# Pro_Micro.net
KiCad netlist of a schematic drawn in EAGLE
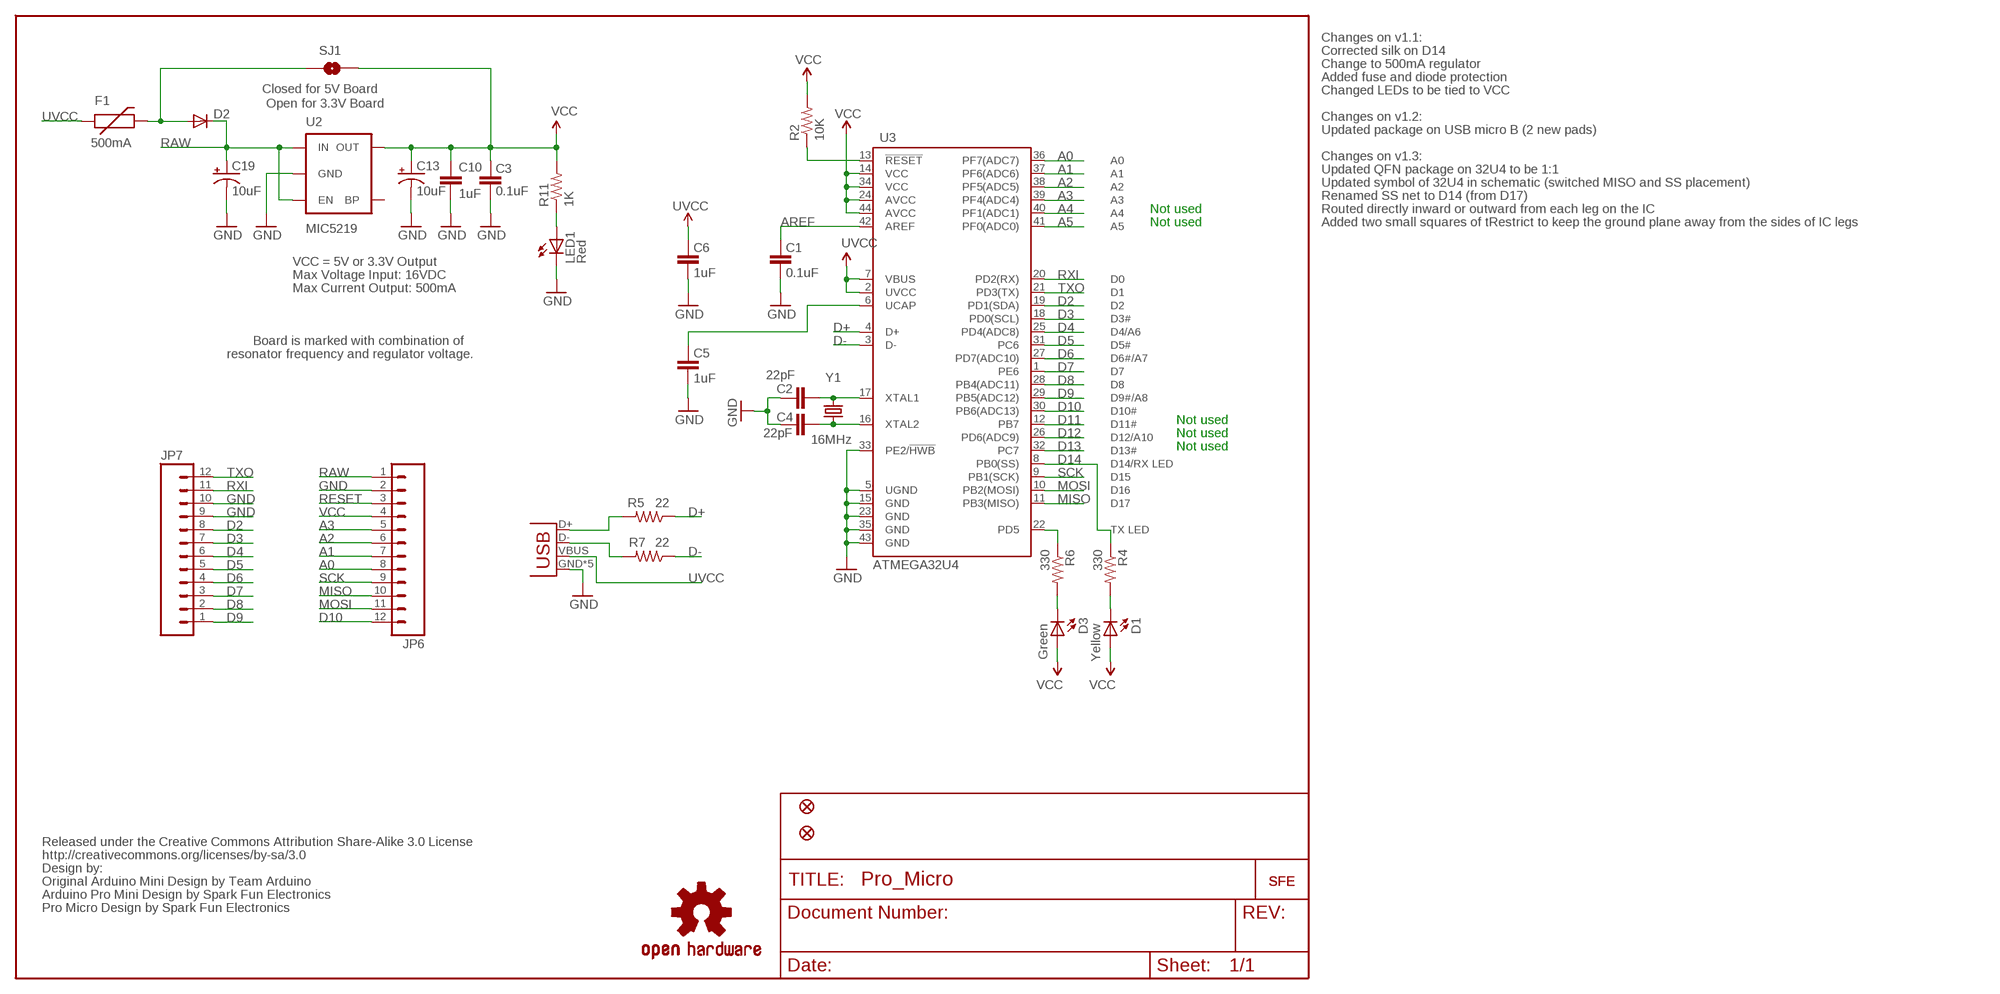
[diagram p0: schematic, sheet 1]

(export (version "E")
  (design (tool "Eeschema 10.0.6"))
  (components
    (comp (ref "C1")
      (value "0.1uF")
      (footprint "eagle-import:0603-CAP")
      (libsource (lib "eagle-import") (part "CAP0603-CAP"))
    )
    (comp (ref "C2")
      (value "22pF")
      (footprint "eagle-import:0603-CAP")
      (libsource (lib "eagle-import") (part "CAP0603-CAP"))
    )
    (comp (ref "C3")
      (value "0.1uF")
      (footprint "eagle-import:0603-CAP")
      (libsource (lib "eagle-import") (part "CAP0603-CAP"))
    )
    (comp (ref "C4")
      (value "22pF")
      (footprint "eagle-import:0603-CAP")
      (libsource (lib "eagle-import") (part "CAP0603-CAP"))
    )
    (comp (ref "C5")
      (value "1uF")
      (footprint "eagle-import:0603-CAP")
      (libsource (lib "eagle-import") (part "CAP0603-CAP"))
    )
    (comp (ref "C6")
      (value "1uF")
      (footprint "eagle-import:0603-CAP")
      (libsource (lib "eagle-import") (part "CAP0603-CAP"))
    )
    (comp (ref "C10")
      (value "1uF")
      (footprint "eagle-import:0603-CAP")
      (libsource (lib "eagle-import") (part "CAP0603-CAP"))
    )
    (comp (ref "C13")
      (value "10uF")
      (footprint "eagle-import:EIA3216")
      (libsource (lib "eagle-import") (part "CAP_POL1206"))
    )
    (comp (ref "C19")
      (value "10uF")
      (footprint "eagle-import:EIA3216")
      (libsource (lib "eagle-import") (part "CAP_POL1206"))
    )
    (comp (ref "D1")
      (value "Yellow")
      (footprint "eagle-import:LED-0603")
      (libsource (lib "eagle-import") (part "LED0603"))
    )
    (comp (ref "D2")
      (value "DIODESOD")
      (footprint "eagle-import:SOD-323")
      (libsource (lib "eagle-import") (part "DIODESOD"))
    )
    (comp (ref "D3")
      (value "Green")
      (footprint "eagle-import:LED-0603")
      (libsource (lib "eagle-import") (part "LED0603"))
    )
    (comp (ref "F1")
      (value "500mA")
      (footprint "eagle-import:PTC-1206")
      (libsource (lib "eagle-import") (part "PTCSMD"))
    )
    (comp (ref "JP1")
      (value "FIDUCIALUFIDUCIAL")
      (footprint "eagle-import:MICRO-FIDUCIAL")
      (libsource (lib "eagle-import") (part "FIDUCIALUFIDUCIAL"))
    )
    (comp (ref "JP2")
      (value "FIDUCIALUFIDUCIAL")
      (footprint "eagle-import:MICRO-FIDUCIAL")
      (libsource (lib "eagle-import") (part "FIDUCIALUFIDUCIAL"))
    )
    (comp (ref "JP6")
      (value "M12PTH")
      (footprint "eagle-import:1X12")
      (libsource (lib "eagle-import") (part "M12PTH"))
    )
    (comp (ref "JP7")
      (value "M12PTH")
      (footprint "eagle-import:1X12")
      (libsource (lib "eagle-import") (part "M12PTH"))
    )
    (comp (ref "LED1")
      (value "Red")
      (footprint "eagle-import:LED-0603")
      (libsource (lib "eagle-import") (part "LED0603"))
    )
    (comp (ref "R2")
      (value "10K")
      (footprint "eagle-import:0603-RES")
      (libsource (lib "eagle-import") (part "RESISTOR0603-RES"))
    )
    (comp (ref "R4")
      (value "330")
      (footprint "eagle-import:0603-RES")
      (libsource (lib "eagle-import") (part "RESISTOR0603-RES"))
    )
    (comp (ref "R5")
      (value "22")
      (footprint "eagle-import:0603-RES")
      (libsource (lib "eagle-import") (part "RESISTOR0603-RES"))
    )
    (comp (ref "R6")
      (value "330")
      (footprint "eagle-import:0603-RES")
      (libsource (lib "eagle-import") (part "RESISTOR0603-RES"))
    )
    (comp (ref "R7")
      (value "22")
      (footprint "eagle-import:0603-RES")
      (libsource (lib "eagle-import") (part "RESISTOR0603-RES"))
    )
    (comp (ref "R11")
      (value "1K")
      (footprint "eagle-import:0603-RES")
      (libsource (lib "eagle-import") (part "RESISTOR0603-RES"))
    )
    (comp (ref "SJ1")
      (value "Closed for 5V Board")
      (footprint "eagle-import:SJ_2S")
      (libsource (lib "eagle-import") (part "SOLDERJUMPERNC"))
    )
    (comp (ref "U$1")
      (value "LOGO-SFESK")
      (footprint "eagle-import:SFE-LOGO-FLAME")
      (libsource (lib "eagle-import") (part "LOGO-SFESK"))
    )
    (comp (ref "U$3")
      (value "OSHW-LOGOS")
      (footprint "eagle-import:OSHW-LOGO-S")
      (libsource (lib "eagle-import") (part "OSHW-LOGOS"))
    )
    (comp (ref "U$5")
      (value "CREATIVE_COMMONS")
      (footprint "eagle-import:CREATIVE_COMMONS")
      (libsource (lib "eagle-import") (part "CREATIVE_COMMONS"))
    )
    (comp (ref "U$11")
      (value "LOGO-SFENEW")
      (footprint "eagle-import:SFE-NEW-WEBLOGO")
      (libsource (lib "eagle-import") (part "LOGO-SFENEW"))
    )
    (comp (ref "U2")
      (value "MIC5219")
      (footprint "eagle-import:SOT23-5")
      (libsource (lib "eagle-import") (part "V_REG_LDOSMD"))
    )
    (comp (ref "U3")
      (value "ATMEGA32U4")
      (footprint "eagle-import:QFN-44-NOPAD_1_1")
      (libsource (lib "eagle-import") (part "ATMEGA32U41{colon}1"))
    )
    (comp (ref "X1")
      (value "USB-MICROB")
      (footprint "eagle-import:USB-MICROB")
      (libsource (lib "eagle-import") (part "USB-MICROB"))
    )
    (comp (ref "Y1")
      (value "16MHz")
      (footprint "eagle-import:CRYSTAL-SMD-5X3")
      (libsource (lib "eagle-import") (part "CRYSTAL5X3"))
    )
  )
  (nets
    (net (code "1") (name "/A0") (class "Default")
      (node (ref "JP6") (pin "8") (pinfunction "8_8") (pintype "passive"))
      (node (ref "U3") (pin "36") (pinfunction "PF7(ADC7)_36") (pintype "bidirectional"))
    )
    (net (code "2") (name "/A1") (class "Default")
      (node (ref "JP6") (pin "7") (pinfunction "7_7") (pintype "passive"))
      (node (ref "U3") (pin "37") (pinfunction "PF6(ADC6)_37") (pintype "bidirectional"))
    )
    (net (code "3") (name "/A2") (class "Default")
      (node (ref "JP6") (pin "6") (pinfunction "6_6") (pintype "passive"))
      (node (ref "U3") (pin "38") (pinfunction "PF5(ADC5)_38") (pintype "bidirectional"))
    )
    (net (code "4") (name "/A3") (class "Default")
      (node (ref "JP6") (pin "5") (pinfunction "5_5") (pintype "passive"))
      (node (ref "U3") (pin "39") (pinfunction "PF4(ADC4)_39") (pintype "bidirectional"))
    )
    (net (code "5") (name "/A4") (class "Default")
      (node (ref "U3") (pin "40") (pinfunction "PF1(ADC1)_40") (pintype "bidirectional"))
    )
    (net (code "6") (name "/A5") (class "Default")
      (node (ref "U3") (pin "41") (pinfunction "PF0(ADC0)_41") (pintype "bidirectional"))
    )
    (net (code "7") (name "/AREF") (class "Default")
      (node (ref "C1") (pin "2") (pinfunction "2_2") (pintype "passive"))
      (node (ref "U3") (pin "42") (pinfunction "AREF_42") (pintype "bidirectional"))
    )
    (net (code "8") (name "/D+") (class "Default")
      (node (ref "R5") (pin "1") (pinfunction "1_1") (pintype "passive"))
      (node (ref "U3") (pin "4") (pinfunction "D+_4") (pintype "bidirectional"))
    )
    (net (code "9") (name "/D-") (class "Default")
      (node (ref "R7") (pin "1") (pinfunction "1_1") (pintype "passive"))
      (node (ref "U3") (pin "3") (pinfunction "D-_3") (pintype "bidirectional"))
    )
    (net (code "10") (name "/D2") (class "Default")
      (node (ref "JP7") (pin "8") (pinfunction "8_8") (pintype "passive"))
      (node (ref "U3") (pin "19") (pinfunction "PD1(SDA)_19") (pintype "bidirectional"))
    )
    (net (code "11") (name "/D3") (class "Default")
      (node (ref "JP7") (pin "7") (pinfunction "7_7") (pintype "passive"))
      (node (ref "U3") (pin "18") (pinfunction "PD0(SCL)_18") (pintype "bidirectional"))
    )
    (net (code "12") (name "/D4") (class "Default")
      (node (ref "JP7") (pin "6") (pinfunction "6_6") (pintype "passive"))
      (node (ref "U3") (pin "25") (pinfunction "PD4(ADC8)_25") (pintype "bidirectional"))
    )
    (net (code "13") (name "/D5") (class "Default")
      (node (ref "JP7") (pin "5") (pinfunction "5_5") (pintype "passive"))
      (node (ref "U3") (pin "31") (pinfunction "PC6_31") (pintype "bidirectional"))
    )
    (net (code "14") (name "/D6") (class "Default")
      (node (ref "JP7") (pin "4") (pinfunction "4_4") (pintype "passive"))
      (node (ref "U3") (pin "27") (pinfunction "PD7(ADC10)_27") (pintype "bidirectional"))
    )
    (net (code "15") (name "/D7") (class "Default")
      (node (ref "JP7") (pin "3") (pinfunction "3_3") (pintype "passive"))
      (node (ref "U3") (pin "1") (pinfunction "PE6_1") (pintype "bidirectional"))
    )
    (net (code "16") (name "/D8") (class "Default")
      (node (ref "JP7") (pin "2") (pinfunction "2_2") (pintype "passive"))
      (node (ref "U3") (pin "28") (pinfunction "PB4(ADC11)_28") (pintype "bidirectional"))
    )
    (net (code "17") (name "/D9") (class "Default")
      (node (ref "JP7") (pin "1") (pinfunction "1_1") (pintype "passive"))
      (node (ref "U3") (pin "29") (pinfunction "PB5(ADC12)_29") (pintype "bidirectional"))
    )
    (net (code "18") (name "/D10") (class "Default")
      (node (ref "JP6") (pin "12") (pinfunction "12_12") (pintype "passive"))
      (node (ref "U3") (pin "30") (pinfunction "PB6(ADC13)_30") (pintype "bidirectional"))
    )
    (net (code "19") (name "/D11") (class "Default")
      (node (ref "U3") (pin "12") (pinfunction "PB7_12") (pintype "bidirectional"))
    )
    (net (code "20") (name "/D12") (class "Default")
      (node (ref "U3") (pin "26") (pinfunction "PD6(ADC9)_26") (pintype "bidirectional"))
    )
    (net (code "21") (name "/D13") (class "Default")
      (node (ref "U3") (pin "32") (pinfunction "PC7_32") (pintype "bidirectional"))
    )
    (net (code "22") (name "/D14") (class "Default")
      (node (ref "R4") (pin "1") (pinfunction "1_1") (pintype "passive"))
      (node (ref "U3") (pin "8") (pinfunction "PB0(SS)_8") (pintype "bidirectional"))
    )
    (net (code "23") (name "/MISO") (class "Default")
      (node (ref "JP6") (pin "10") (pinfunction "10_10") (pintype "passive"))
      (node (ref "U3") (pin "11") (pinfunction "PB3(MISO)_11") (pintype "bidirectional"))
    )
    (net (code "24") (name "/MOSI") (class "Default")
      (node (ref "JP6") (pin "11") (pinfunction "11_11") (pintype "passive"))
      (node (ref "U3") (pin "10") (pinfunction "PB2(MOSI)_10") (pintype "bidirectional"))
    )
    (net (code "25") (name "/RAW") (class "Default")
      (node (ref "C19") (pin "A") (pinfunction "+_A") (pintype "passive"))
      (node (ref "D2") (pin "1") (pinfunction "C_1") (pintype "passive"))
      (node (ref "JP6") (pin "1") (pinfunction "1_1") (pintype "passive"))
      (node (ref "U2") (pin "1") (pinfunction "IN_1") (pintype "input"))
      (node (ref "U2") (pin "3") (pinfunction "EN_3") (pintype "input"))
    )
    (net (code "26") (name "/RESET") (class "Default")
      (node (ref "JP6") (pin "3") (pinfunction "3_3") (pintype "passive"))
      (node (ref "R2") (pin "1") (pinfunction "1_1") (pintype "passive"))
      (node (ref "U3") (pin "13") (pinfunction "~{RESET}_13") (pintype "bidirectional"))
    )
    (net (code "27") (name "/RXI") (class "Default")
      (node (ref "JP7") (pin "11") (pinfunction "11_11") (pintype "passive"))
      (node (ref "U3") (pin "20") (pinfunction "PD2(RX)_20") (pintype "bidirectional"))
    )
    (net (code "28") (name "/SCK") (class "Default")
      (node (ref "JP6") (pin "9") (pinfunction "9_9") (pintype "passive"))
      (node (ref "U3") (pin "9") (pinfunction "PB1(SCK)_9") (pintype "bidirectional"))
    )
    (net (code "29") (name "/TXO") (class "Default")
      (node (ref "JP7") (pin "12") (pinfunction "12_12") (pintype "passive"))
      (node (ref "U3") (pin "21") (pinfunction "PD3(TX)_21") (pintype "bidirectional"))
    )
    (net (code "30") (name "GND") (class "Default")
      (node (ref "C1") (pin "1") (pinfunction "1_1") (pintype "passive"))
      (node (ref "C10") (pin "2") (pinfunction "2_2") (pintype "passive"))
      (node (ref "C13") (pin "C") (pinfunction "-_C") (pintype "passive"))
      (node (ref "C19") (pin "C") (pinfunction "-_C") (pintype "passive"))
      (node (ref "C2") (pin "2") (pinfunction "2_2") (pintype "passive"))
      (node (ref "C3") (pin "1") (pinfunction "1_1") (pintype "passive"))
      (node (ref "C4") (pin "2") (pinfunction "2_2") (pintype "passive"))
      (node (ref "C5") (pin "1") (pinfunction "1_1") (pintype "passive"))
      (node (ref "C6") (pin "1") (pinfunction "1_1") (pintype "passive"))
      (node (ref "JP6") (pin "2") (pinfunction "2_2") (pintype "passive"))
      (node (ref "JP7") (pin "10") (pinfunction "10_10") (pintype "passive"))
      (node (ref "JP7") (pin "9") (pinfunction "9_9") (pintype "passive"))
      (node (ref "LED1") (pin "C") (pinfunction "C_C") (pintype "passive"))
      (node (ref "U2") (pin "2") (pinfunction "GND_2") (pintype "input"))
      (node (ref "U3") (pin "15") (pinfunction "GND_15") (pintype "bidirectional"))
      (node (ref "U3") (pin "23") (pinfunction "GND_23") (pintype "bidirectional"))
      (node (ref "U3") (pin "33") (pinfunction "PE2/~{HWB}_33") (pintype "bidirectional"))
      (node (ref "U3") (pin "35") (pinfunction "GND_35") (pintype "bidirectional"))
      (node (ref "U3") (pin "43") (pinfunction "GND_43") (pintype "bidirectional"))
      (node (ref "U3") (pin "5") (pinfunction "UGND_5") (pintype "bidirectional"))
      (node (ref "X1") (pin "GND") (pinfunction "GND_GND") (pintype "bidirectional"))
      (node (ref "X1") (pin "MT1") (pinfunction "GND_MT1") (pintype "bidirectional"))
      (node (ref "X1") (pin "MT2") (pinfunction "GND_MT2") (pintype "bidirectional"))
      (node (ref "X1") (pin "MT3") (pinfunction "GND_MT3") (pintype "bidirectional"))
      (node (ref "X1") (pin "MT4") (pinfunction "GND_MT4") (pintype "bidirectional"))
    )
    (net (code "31") (name "Net-(D1-PadC)") (class "Default")
      (node (ref "D1") (pin "C") (pinfunction "C_C") (pintype "passive"))
      (node (ref "R4") (pin "2") (pinfunction "2_2") (pintype "passive"))
    )
    (net (code "32") (name "Net-(D2-A)") (class "Default")
      (node (ref "D2") (pin "2") (pinfunction "A_2") (pintype "passive"))
      (node (ref "F1") (pin "2") (pinfunction "2_2") (pintype "bidirectional"))
      (node (ref "SJ1") (pin "1") (pinfunction "1_1") (pintype "passive"))
    )
    (net (code "33") (name "Net-(D3-PadC)") (class "Default")
      (node (ref "D3") (pin "C") (pinfunction "C_C") (pintype "passive"))
      (node (ref "R6") (pin "2") (pinfunction "2_2") (pintype "passive"))
    )
    (net (code "34") (name "Net-(LED1-PadA)") (class "Default")
      (node (ref "LED1") (pin "A") (pinfunction "A_A") (pintype "passive"))
      (node (ref "R11") (pin "1") (pinfunction "1_1") (pintype "passive"))
    )
    (net (code "35") (name "Net-(R5-Pad2)") (class "Default")
      (node (ref "R5") (pin "2") (pinfunction "2_2") (pintype "passive"))
      (node (ref "X1") (pin "D+") (pinfunction "D+_D+") (pintype "bidirectional"))
    )
    (net (code "36") (name "Net-(R7-Pad2)") (class "Default")
      (node (ref "R7") (pin "2") (pinfunction "2_2") (pintype "passive"))
      (node (ref "X1") (pin "D-") (pinfunction "D-_D-") (pintype "bidirectional"))
    )
    (net (code "37") (name "Net-(U3-PD5)") (class "Default")
      (node (ref "R6") (pin "1") (pinfunction "1_1") (pintype "passive"))
      (node (ref "U3") (pin "22") (pinfunction "PD5_22") (pintype "bidirectional"))
    )
    (net (code "38") (name "Net-(U3-UCAP)") (class "Default")
      (node (ref "C5") (pin "2") (pinfunction "2_2") (pintype "passive"))
      (node (ref "U3") (pin "6") (pinfunction "UCAP_6") (pintype "bidirectional"))
    )
    (net (code "39") (name "Net-(U3-XTAL1)") (class "Default")
      (node (ref "C2") (pin "1") (pinfunction "1_1") (pintype "passive"))
      (node (ref "U3") (pin "17") (pinfunction "XTAL1_17") (pintype "bidirectional"))
      (node (ref "Y1") (pin "3") (pinfunction "2_3") (pintype "passive"))
    )
    (net (code "40") (name "Net-(U3-XTAL2)") (class "Default")
      (node (ref "C4") (pin "1") (pinfunction "1_1") (pintype "passive"))
      (node (ref "U3") (pin "16") (pinfunction "XTAL2_16") (pintype "bidirectional"))
      (node (ref "Y1") (pin "1") (pinfunction "1_1") (pintype "passive"))
    )
    (net (code "41") (name "UVCC") (class "Default")
      (node (ref "C6") (pin "2") (pinfunction "2_2") (pintype "passive"))
      (node (ref "F1") (pin "1") (pinfunction "1_1") (pintype "bidirectional"))
      (node (ref "U3") (pin "2") (pinfunction "UVCC_2") (pintype "bidirectional"))
      (node (ref "U3") (pin "7") (pinfunction "VBUS_7") (pintype "bidirectional"))
      (node (ref "X1") (pin "VBUS") (pinfunction "VBUS_VBUS") (pintype "bidirectional"))
    )
    (net (code "42") (name "VCC") (class "Default")
      (node (ref "C10") (pin "1") (pinfunction "1_1") (pintype "passive"))
      (node (ref "C13") (pin "A") (pinfunction "+_A") (pintype "passive"))
      (node (ref "C3") (pin "2") (pinfunction "2_2") (pintype "passive"))
      (node (ref "D1") (pin "A") (pinfunction "A_A") (pintype "passive"))
      (node (ref "D3") (pin "A") (pinfunction "A_A") (pintype "passive"))
      (node (ref "JP6") (pin "4") (pinfunction "4_4") (pintype "passive"))
      (node (ref "R11") (pin "2") (pinfunction "2_2") (pintype "passive"))
      (node (ref "R2") (pin "2") (pinfunction "2_2") (pintype "passive"))
      (node (ref "SJ1") (pin "2") (pinfunction "2_2") (pintype "passive"))
      (node (ref "U2") (pin "5") (pinfunction "OUT_5") (pintype "passive"))
      (node (ref "U3") (pin "14") (pinfunction "VCC_14") (pintype "bidirectional"))
      (node (ref "U3") (pin "24") (pinfunction "AVCC_24") (pintype "bidirectional"))
      (node (ref "U3") (pin "34") (pinfunction "VCC_34") (pintype "bidirectional"))
      (node (ref "U3") (pin "44") (pinfunction "AVCC_44") (pintype "bidirectional"))
    )
    (net (code "43") (name "unconnected-(U2-BP-Pad4)") (class "Default")
      (node (ref "U2") (pin "4") (pinfunction "BP_4") (pintype "input"))
    )
  )
)
